# usb2serial-pic14f1454.net
KiCad netlist of a schematic drawn in EAGLE
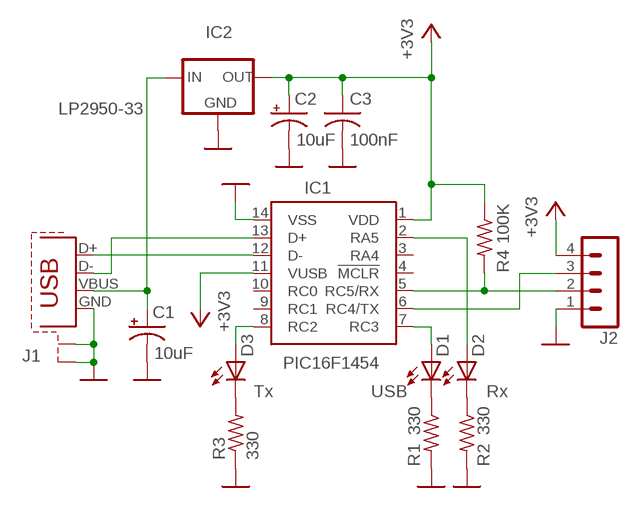
[diagram p0: schematic, sheet 1]

(export (version "E")
  (design (tool "Eeschema 10.0.6"))
  (components
    (comp (ref "C1")
      (value "10uF")
      (footprint "eagle-import:E2-4")
      (libsource (lib "eagle-import") (part "CPOL-USE2-4"))
    )
    (comp (ref "C2")
      (value "10uF")
      (footprint "eagle-import:E2-4")
      (libsource (lib "eagle-import") (part "CPOL-USE2-4"))
    )
    (comp (ref "C3")
      (value "100nF")
      (footprint "eagle-import:C050-025X075")
      (libsource (lib "eagle-import") (part "C-US050-025X075"))
    )
    (comp (ref "D1")
      (value "LED5MM")
      (footprint "eagle-import:LED5MM")
      (libsource (lib "eagle-import") (part "LED5MM"))
    )
    (comp (ref "D2")
      (value "LED5MM")
      (footprint "eagle-import:LED5MM")
      (libsource (lib "eagle-import") (part "LED5MM"))
    )
    (comp (ref "D3")
      (value "LED5MM")
      (footprint "eagle-import:LED5MM")
      (libsource (lib "eagle-import") (part "LED5MM"))
    )
    (comp (ref "IC1")
      (value "PIC16F1454")
      (footprint "eagle-import:DIL14")
      (libsource (lib "eagle-import") (part "PIC16F1454"))
    )
    (comp (ref "IC2")
      (value "LP2950-33")
      (footprint "eagle-import:78LXX")
      (libsource (lib "eagle-import") (part "78LXX"))
    )
    (comp (ref "J1")
      (value "USB-SHIELD-A-H")
      (footprint "eagle-import:USB-A-H")
      (libsource (lib "eagle-import") (part "USB-SHIELD-A-H"))
    )
    (comp (ref "J2")
      (value "J2")
      (footprint "eagle-import:MA04-1")
      (libsource (lib "eagle-import") (part "MA04-1"))
    )
    (comp (ref "R1")
      (value "330")
      (footprint "eagle-import:0207_10")
      (libsource (lib "eagle-import") (part "R-US_0207/10"))
    )
    (comp (ref "R2")
      (value "330")
      (footprint "eagle-import:0207_10")
      (libsource (lib "eagle-import") (part "R-US_0207/10"))
    )
    (comp (ref "R3")
      (value "330")
      (footprint "eagle-import:0207_10")
      (libsource (lib "eagle-import") (part "R-US_0207/10"))
    )
    (comp (ref "R4")
      (value "100K")
      (footprint "eagle-import:0207_10")
      (libsource (lib "eagle-import") (part "R-US_0207/10"))
    )
  )
  (nets
    (net (code "1") (name "+3V3") (class "Default")
      (node (ref "C2") (pin "+") (pinfunction "+_+") (pintype "passive"))
      (node (ref "C3") (pin "1") (pinfunction "1_1") (pintype "passive"))
      (node (ref "IC1") (pin "1") (pinfunction "VDD_1") (pintype "power_in"))
      (node (ref "IC1") (pin "11") (pinfunction "VUSB_11") (pintype "power_in"))
      (node (ref "IC2") (pin "OUT") (pinfunction "OUT_OUT") (pintype "passive"))
      (node (ref "J2") (pin "4") (pinfunction "4_4") (pintype "passive"))
      (node (ref "R4") (pin "1") (pinfunction "1_1") (pintype "passive"))
    )
    (net (code "2") (name "GND") (class "Default")
      (node (ref "C1") (pin "-") (pinfunction "-_-") (pintype "passive"))
      (node (ref "C2") (pin "-") (pinfunction "-_-") (pintype "passive"))
      (node (ref "C3") (pin "2") (pinfunction "2_2") (pintype "passive"))
      (node (ref "IC1") (pin "14") (pinfunction "VSS_14") (pintype "power_in"))
      (node (ref "IC2") (pin "GND") (pinfunction "GND_GND") (pintype "input"))
      (node (ref "J1") (pin "GND") (pinfunction "GND_GND") (pintype "passive"))
      (node (ref "J1") (pin "GND2") (pinfunction "S1_GND2") (pintype "passive"))
      (node (ref "J1") (pin "GND3") (pinfunction "S2_GND3") (pintype "passive"))
      (node (ref "J2") (pin "1") (pinfunction "1_1") (pintype "passive"))
      (node (ref "R1") (pin "2") (pinfunction "2_2") (pintype "passive"))
      (node (ref "R2") (pin "2") (pinfunction "2_2") (pintype "passive"))
      (node (ref "R3") (pin "1") (pinfunction "1_1") (pintype "passive"))
    )
    (net (code "3") (name "Net-(C1-Pad+)") (class "Default")
      (node (ref "C1") (pin "+") (pinfunction "+_+") (pintype "passive"))
      (node (ref "IC2") (pin "IN") (pinfunction "IN_IN") (pintype "input"))
      (node (ref "J1") (pin "VBUS") (pinfunction "VBUS_VBUS") (pintype "passive"))
    )
    (net (code "4") (name "Net-(D1-C)") (class "Default")
      (node (ref "D1") (pin "K") (pinfunction "C_K") (pintype "passive"))
      (node (ref "R1") (pin "1") (pinfunction "1_1") (pintype "passive"))
    )
    (net (code "5") (name "Net-(D2-C)") (class "Default")
      (node (ref "D2") (pin "K") (pinfunction "C_K") (pintype "passive"))
      (node (ref "R2") (pin "1") (pinfunction "1_1") (pintype "passive"))
    )
    (net (code "6") (name "Net-(D3-C)") (class "Default")
      (node (ref "D3") (pin "K") (pinfunction "C_K") (pintype "passive"))
      (node (ref "R3") (pin "2") (pinfunction "2_2") (pintype "passive"))
    )
    (net (code "7") (name "Net-(IC1-D+)") (class "Default")
      (node (ref "IC1") (pin "13") (pinfunction "D+_13") (pintype "passive"))
      (node (ref "J1") (pin "D-") (pinfunction "D-_D-") (pintype "passive"))
    )
    (net (code "8") (name "Net-(IC1-D-)") (class "Default")
      (node (ref "IC1") (pin "12") (pinfunction "D-_12") (pintype "passive"))
      (node (ref "J1") (pin "D+") (pinfunction "D+_D+") (pintype "passive"))
    )
    (net (code "9") (name "Net-(IC1-RA5)") (class "Default")
      (node (ref "D2") (pin "A") (pinfunction "A_A") (pintype "passive"))
      (node (ref "IC1") (pin "2") (pinfunction "RA5_2") (pintype "bidirectional"))
    )
    (net (code "10") (name "Net-(IC1-RC2)") (class "Default")
      (node (ref "D3") (pin "A") (pinfunction "A_A") (pintype "passive"))
      (node (ref "IC1") (pin "8") (pinfunction "RC2_8") (pintype "bidirectional"))
    )
    (net (code "11") (name "Net-(IC1-RC3)") (class "Default")
      (node (ref "D1") (pin "A") (pinfunction "A_A") (pintype "passive"))
      (node (ref "IC1") (pin "7") (pinfunction "RC3_7") (pintype "bidirectional"))
    )
    (net (code "12") (name "Net-(IC1-RC4{slash}TX)") (class "Default")
      (node (ref "IC1") (pin "6") (pinfunction "RC4/TX_6") (pintype "input"))
      (node (ref "J2") (pin "3") (pinfunction "3_3") (pintype "passive"))
    )
    (net (code "13") (name "Net-(IC1-RC5{slash}RX)") (class "Default")
      (node (ref "IC1") (pin "5") (pinfunction "RC5/RX_5") (pintype "bidirectional"))
      (node (ref "J2") (pin "2") (pinfunction "2_2") (pintype "passive"))
      (node (ref "R4") (pin "2") (pinfunction "2_2") (pintype "passive"))
    )
    (net (code "14") (name "unconnected-(IC1-RA4-Pad3)") (class "Default")
      (node (ref "IC1") (pin "3") (pinfunction "RA4_3") (pintype "bidirectional"))
    )
    (net (code "15") (name "unconnected-(IC1-RC0-Pad10)") (class "Default")
      (node (ref "IC1") (pin "10") (pinfunction "RC0_10") (pintype "bidirectional"))
    )
    (net (code "16") (name "unconnected-(IC1-RC1-Pad9)") (class "Default")
      (node (ref "IC1") (pin "9") (pinfunction "RC1_9") (pintype "bidirectional"))
    )
    (net (code "17") (name "unconnected-(IC1-~{MCLR}-Pad4)") (class "Default")
      (node (ref "IC1") (pin "4") (pinfunction "~{MCLR}_4") (pintype "bidirectional"))
    )
  )
)
